# joyAnalog.net
KiCad netlist of a schematic drawn in EAGLE
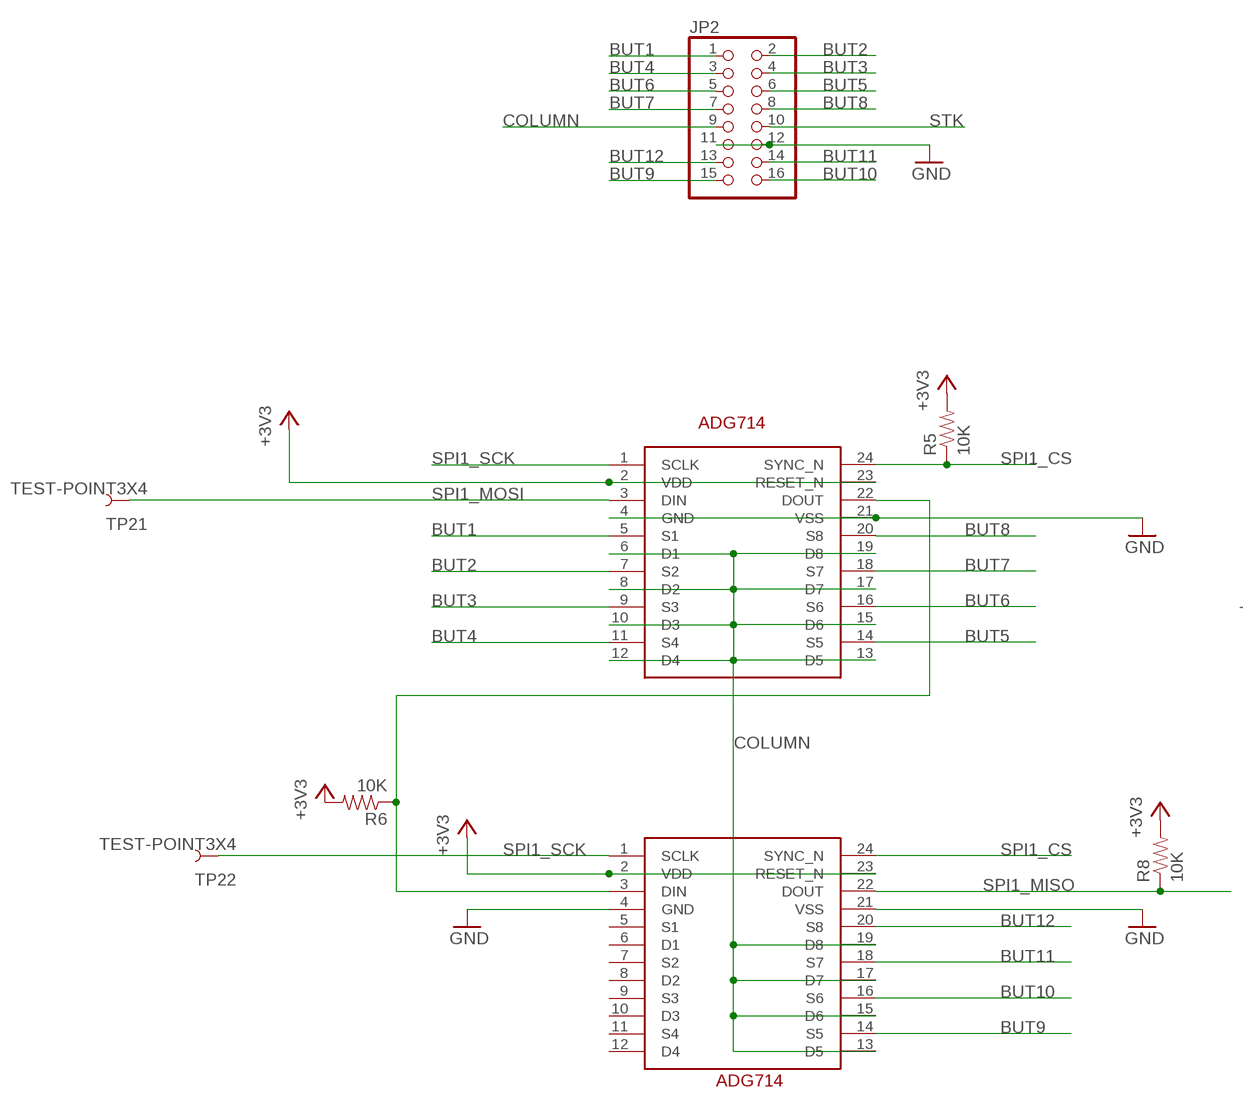
[diagram p0: schematic, sheet 1, part 1 of 2]
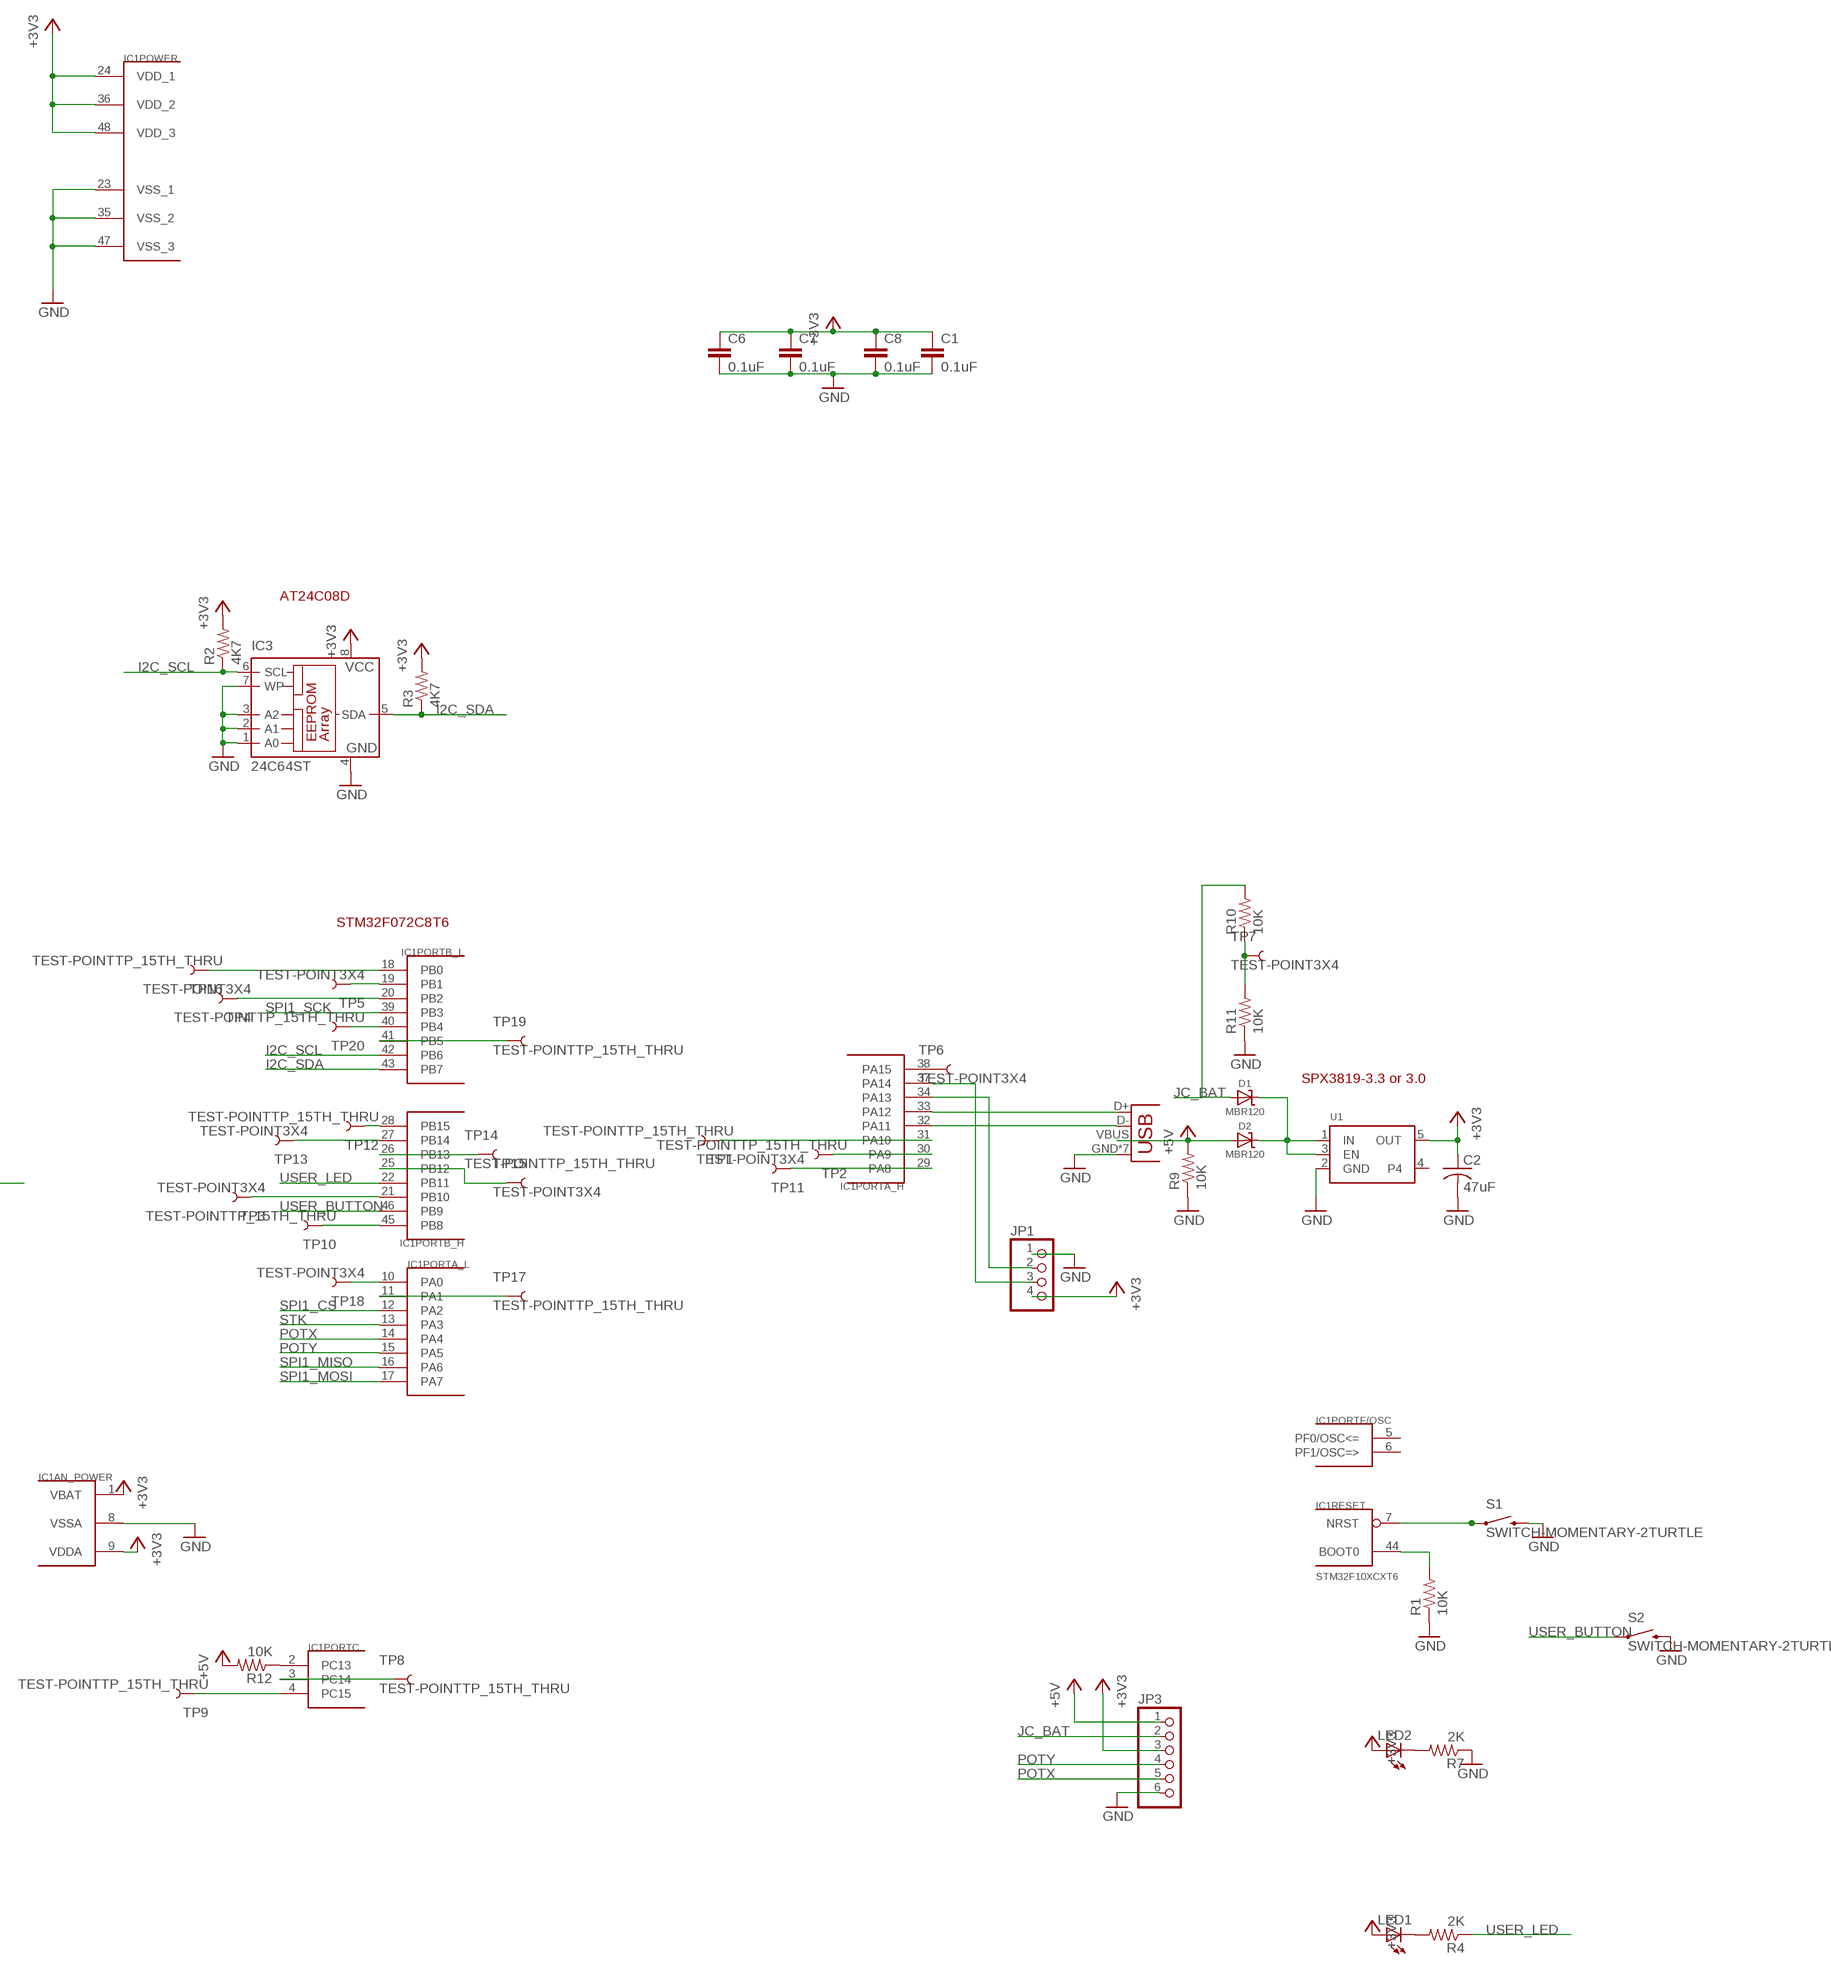
[diagram p1: schematic, sheet 1, part 2 of 2]

(export (version "E")
  (design (tool "Eeschema 10.0.6"))
  (components
    (comp (ref "C1")
      (value "0.1uF")
      (footprint "eagle-import:0805")
      (libsource (lib "eagle-import") (part "CAP0805"))
    )
    (comp (ref "C2")
      (value "47uF")
      (footprint "eagle-import:C1210")
      (libsource (lib "eagle-import") (part "C-USC1210"))
    )
    (comp (ref "C6")
      (value "0.1uF")
      (footprint "eagle-import:0805")
      (libsource (lib "eagle-import") (part "CAP0805"))
    )
    (comp (ref "C7")
      (value "0.1uF")
      (footprint "eagle-import:0805")
      (libsource (lib "eagle-import") (part "CAP0805"))
    )
    (comp (ref "C8")
      (value "0.1uF")
      (footprint "eagle-import:0805")
      (libsource (lib "eagle-import") (part "CAP0805"))
    )
    (comp (ref "D1")
      (value "MBR120")
      (footprint "eagle-import:SOD-123")
      (libsource (lib "eagle-import") (part "DIODE-SCHOTTKYSOD-123"))
    )
    (comp (ref "D2")
      (value "MBR120")
      (footprint "eagle-import:SOD-123")
      (libsource (lib "eagle-import") (part "DIODE-SCHOTTKYSOD-123"))
    )
    (comp (ref "IC1")
      (value "STM32F10XCXT6")
      (footprint "eagle-import:TQFP48")
      (libsource (lib "eagle-import") (part "STM32F10XCXT6"))
    )
    (comp (ref "IC3")
      (value "24C64ST")
      (footprint "eagle-import:TSSOP8")
      (fields (field (name "MPN") "CAT24C64YI-GT3"))
      (libsource (lib "eagle-import") (part "24STC64"))
    )
    (comp (ref "JP1")
      (value "PINHD-1X4")
      (footprint "eagle-import:1X04")
      (libsource (lib "eagle-import") (part "PINHD-1X4"))
    )
    (comp (ref "JP2")
      (value "PINHD-2X8")
      (footprint "eagle-import:2X08")
      (libsource (lib "eagle-import") (part "PINHD-2X8"))
    )
    (comp (ref "JP3")
      (value "PINHD-1X6CB")
      (footprint "eagle-import:1X06-CLEANBIG")
      (libsource (lib "eagle-import") (part "PINHD-1X6CB"))
    )
    (comp (ref "LED1")
      (value "LEDCHIP-LED0805")
      (footprint "eagle-import:CHIP-LED0805")
      (libsource (lib "eagle-import") (part "LEDCHIP-LED0805"))
    )
    (comp (ref "LED2")
      (value "LEDCHIP-LED0805")
      (footprint "eagle-import:CHIP-LED0805")
      (libsource (lib "eagle-import") (part "LEDCHIP-LED0805"))
    )
    (comp (ref "R1")
      (value "10K")
      (footprint "eagle-import:0805")
      (libsource (lib "eagle-import") (part "RESISTOR0805-RES"))
    )
    (comp (ref "R2")
      (value "4K7")
      (footprint "eagle-import:0805")
      (libsource (lib "eagle-import") (part "RESISTOR0805-RES"))
    )
    (comp (ref "R3")
      (value "4K7")
      (footprint "eagle-import:0805")
      (libsource (lib "eagle-import") (part "RESISTOR0805-RES"))
    )
    (comp (ref "R4")
      (value "2K")
      (footprint "eagle-import:0805")
      (libsource (lib "eagle-import") (part "RESISTOR0805-RES"))
    )
    (comp (ref "R5")
      (value "10K")
      (footprint "eagle-import:0805")
      (libsource (lib "eagle-import") (part "RESISTOR0805-RES"))
    )
    (comp (ref "R6")
      (value "10K")
      (footprint "eagle-import:0805")
      (libsource (lib "eagle-import") (part "RESISTOR0805-RES"))
    )
    (comp (ref "R7")
      (value "2K")
      (footprint "eagle-import:0805")
      (libsource (lib "eagle-import") (part "RESISTOR0805-RES"))
    )
    (comp (ref "R8")
      (value "10K")
      (footprint "eagle-import:0805")
      (libsource (lib "eagle-import") (part "RESISTOR0805-RES"))
    )
    (comp (ref "R9")
      (value "10K")
      (footprint "eagle-import:0805")
      (libsource (lib "eagle-import") (part "RESISTOR0805-RES"))
    )
    (comp (ref "R10")
      (value "10K")
      (footprint "eagle-import:0805")
      (libsource (lib "eagle-import") (part "RESISTOR0805-RES"))
    )
    (comp (ref "R11")
      (value "10K")
      (footprint "eagle-import:0805")
      (libsource (lib "eagle-import") (part "RESISTOR0805-RES"))
    )
    (comp (ref "R12")
      (value "10K")
      (footprint "eagle-import:0805")
      (libsource (lib "eagle-import") (part "RESISTOR0805-RES"))
    )
    (comp (ref "S1")
      (value "SWITCH-MOMENTARY-2TURTLE")
      (footprint "eagle-import:KMR2")
      (libsource (lib "eagle-import") (part "SWITCH-MOMENTARY-2TURTLE"))
    )
    (comp (ref "S2")
      (value "SWITCH-MOMENTARY-2TURTLE")
      (footprint "eagle-import:KMR2")
      (libsource (lib "eagle-import") (part "SWITCH-MOMENTARY-2TURTLE"))
    )
    (comp (ref "TP1")
      (value "TEST-POINTTP_15TH_THRU")
      (footprint "eagle-import:TP_15TH")
      (libsource (lib "eagle-import") (part "pth testpoint_TEST-POINTTP_15TH_THRU"))
    )
    (comp (ref "TP2")
      (value "TEST-POINTTP_15TH_THRU")
      (footprint "eagle-import:TP_15TH")
      (libsource (lib "eagle-import") (part "pth testpoint_TEST-POINTTP_15TH_THRU"))
    )
    (comp (ref "TP3")
      (value "TEST-POINT3X4")
      (footprint "eagle-import:PAD.03X.04")
      (libsource (lib "eagle-import") (part "TEST-POINT3X4"))
    )
    (comp (ref "TP4")
      (value "TEST-POINT3X4")
      (footprint "eagle-import:PAD.03X.04")
      (libsource (lib "eagle-import") (part "TEST-POINT3X4"))
    )
    (comp (ref "TP5")
      (value "TEST-POINT3X4")
      (footprint "eagle-import:PAD.03X.04")
      (libsource (lib "eagle-import") (part "TEST-POINT3X4"))
    )
    (comp (ref "TP6")
      (value "TEST-POINT3X4")
      (footprint "eagle-import:PAD.03X.04")
      (libsource (lib "eagle-import") (part "TEST-POINT3X4"))
    )
    (comp (ref "TP7")
      (value "TEST-POINT3X4")
      (footprint "eagle-import:PAD.03X.04")
      (libsource (lib "eagle-import") (part "TEST-POINT3X4"))
    )
    (comp (ref "TP8")
      (value "TEST-POINTTP_15TH_THRU")
      (footprint "eagle-import:TP_15TH")
      (libsource (lib "eagle-import") (part "pth testpoint_TEST-POINTTP_15TH_THRU"))
    )
    (comp (ref "TP9")
      (value "TEST-POINTTP_15TH_THRU")
      (footprint "eagle-import:TP_15TH")
      (libsource (lib "eagle-import") (part "pth testpoint_TEST-POINTTP_15TH_THRU"))
    )
    (comp (ref "TP10")
      (value "TEST-POINTTP_15TH_THRU")
      (footprint "eagle-import:TP_15TH")
      (libsource (lib "eagle-import") (part "pth testpoint_TEST-POINTTP_15TH_THRU"))
    )
    (comp (ref "TP11")
      (value "TEST-POINT3X4")
      (footprint "eagle-import:PAD.03X.04")
      (libsource (lib "eagle-import") (part "TEST-POINT3X4"))
    )
    (comp (ref "TP12")
      (value "TEST-POINTTP_15TH_THRU")
      (footprint "eagle-import:TP_15TH")
      (libsource (lib "eagle-import") (part "pth testpoint_TEST-POINTTP_15TH_THRU"))
    )
    (comp (ref "TP13")
      (value "TEST-POINT3X4")
      (footprint "eagle-import:PAD.03X.04")
      (libsource (lib "eagle-import") (part "TEST-POINT3X4"))
    )
    (comp (ref "TP14")
      (value "TEST-POINTTP_15TH_THRU")
      (footprint "eagle-import:TP_15TH")
      (libsource (lib "eagle-import") (part "pth testpoint_TEST-POINTTP_15TH_THRU"))
    )
    (comp (ref "TP15")
      (value "TEST-POINT3X4")
      (footprint "eagle-import:PAD.03X.04")
      (libsource (lib "eagle-import") (part "TEST-POINT3X4"))
    )
    (comp (ref "TP16")
      (value "TEST-POINTTP_15TH_THRU")
      (footprint "eagle-import:TP_15TH")
      (libsource (lib "eagle-import") (part "pth testpoint_TEST-POINTTP_15TH_THRU"))
    )
    (comp (ref "TP17")
      (value "TEST-POINTTP_15TH_THRU")
      (footprint "eagle-import:TP_15TH")
      (libsource (lib "eagle-import") (part "pth testpoint_TEST-POINTTP_15TH_THRU"))
    )
    (comp (ref "TP18")
      (value "TEST-POINT3X4")
      (footprint "eagle-import:PAD.03X.04")
      (libsource (lib "eagle-import") (part "TEST-POINT3X4"))
    )
    (comp (ref "TP19")
      (value "TEST-POINTTP_15TH_THRU")
      (footprint "eagle-import:TP_15TH")
      (libsource (lib "eagle-import") (part "pth testpoint_TEST-POINTTP_15TH_THRU"))
    )
    (comp (ref "TP20")
      (value "TEST-POINTTP_15TH_THRU")
      (footprint "eagle-import:TP_15TH")
      (libsource (lib "eagle-import") (part "pth testpoint_TEST-POINTTP_15TH_THRU"))
    )
    (comp (ref "TP21")
      (value "TEST-POINT3X4")
      (footprint "eagle-import:PAD.03X.04")
      (libsource (lib "eagle-import") (part "TEST-POINT3X4"))
    )
    (comp (ref "TP22")
      (value "TEST-POINT3X4")
      (footprint "eagle-import:PAD.03X.04")
      (libsource (lib "eagle-import") (part "TEST-POINT3X4"))
    )
    (comp (ref "U$3")
      (value "ADG714_DEV")
      (footprint "eagle-import:TSSOP-24")
      (libsource (lib "eagle-import") (part "ADG714_DEV"))
    )
    (comp (ref "U$4")
      (value "ADG714_DEV")
      (footprint "eagle-import:TSSOP-24")
      (libsource (lib "eagle-import") (part "ADG714_DEV"))
    )
    (comp (ref "U1")
      (value "VREG_SOT23-5")
      (footprint "eagle-import:SOT23-5")
      (libsource (lib "eagle-import") (part "VREG_SOT23-5"))
    )
    (comp (ref "X1")
      (value "USB-MICROB")
      (footprint "eagle-import:USB-MICROB")
      (libsource (lib "eagle-import") (part "USB-MICROB"))
    )
  )
  (nets
    (net (code "1") (name "+3V3") (class "Default")
      (node (ref "C1") (pin "1") (pinfunction "1_1") (pintype "passive"))
      (node (ref "C2") (pin "1") (pinfunction "1_1") (pintype "passive"))
      (node (ref "C6") (pin "1") (pinfunction "1_1") (pintype "passive"))
      (node (ref "C7") (pin "1") (pinfunction "1_1") (pintype "passive"))
      (node (ref "C8") (pin "1") (pinfunction "1_1") (pintype "passive"))
      (node (ref "IC1") (pin "1") (pinfunction "VBAT_1") (pintype "power_in"))
      (node (ref "IC1") (pin "24") (pinfunction "VDD_1_24") (pintype "power_in"))
      (node (ref "IC1") (pin "36") (pinfunction "VDD_2_36") (pintype "power_in"))
      (node (ref "IC1") (pin "48") (pinfunction "VDD_3_48") (pintype "power_in"))
      (node (ref "IC1") (pin "9") (pinfunction "VDDA_9") (pintype "power_in"))
      (node (ref "IC3") (pin "8") (pinfunction "VCC_8") (pintype "power_in"))
      (node (ref "JP1") (pin "4") (pinfunction "4_4") (pintype "passive"))
      (node (ref "JP3") (pin "3") (pinfunction "3_3") (pintype "passive"))
      (node (ref "LED1") (pin "A") (pinfunction "A_A") (pintype "passive"))
      (node (ref "LED2") (pin "A") (pinfunction "A_A") (pintype "passive"))
      (node (ref "R2") (pin "2") (pinfunction "2_2") (pintype "passive"))
      (node (ref "R3") (pin "2") (pinfunction "2_2") (pintype "passive"))
      (node (ref "R5") (pin "2") (pinfunction "2_2") (pintype "passive"))
      (node (ref "R6") (pin "2") (pinfunction "2_2") (pintype "passive"))
      (node (ref "R8") (pin "2") (pinfunction "2_2") (pintype "passive"))
      (node (ref "U$3") (pin "2") (pinfunction "VDD_2") (pintype "bidirectional"))
      (node (ref "U$3") (pin "23") (pinfunction "RESET_N_23") (pintype "bidirectional"))
      (node (ref "U$4") (pin "2") (pinfunction "VDD_2") (pintype "bidirectional"))
      (node (ref "U$4") (pin "23") (pinfunction "RESET_N_23") (pintype "bidirectional"))
      (node (ref "U1") (pin "5") (pinfunction "OUT_5") (pintype "power_in"))
    )
    (net (code "2") (name "+5V") (class "Default")
      (node (ref "D2") (pin "A") (pinfunction "A_A") (pintype "passive"))
      (node (ref "JP3") (pin "1") (pinfunction "1_1") (pintype "passive"))
      (node (ref "R12") (pin "2") (pinfunction "2_2") (pintype "passive"))
      (node (ref "R9") (pin "2") (pinfunction "2_2") (pintype "passive"))
      (node (ref "X1") (pin "VBUS") (pinfunction "VBUS_VBUS") (pintype "bidirectional"))
    )
    (net (code "3") (name "/BUT1") (class "Default")
      (node (ref "JP2") (pin "1") (pinfunction "1_1") (pintype "passive"))
      (node (ref "U$3") (pin "5") (pinfunction "S1_5") (pintype "bidirectional"))
    )
    (net (code "4") (name "/BUT2") (class "Default")
      (node (ref "JP2") (pin "2") (pinfunction "2_2") (pintype "passive"))
      (node (ref "U$3") (pin "7") (pinfunction "S2_7") (pintype "bidirectional"))
    )
    (net (code "5") (name "/BUT3") (class "Default")
      (node (ref "JP2") (pin "4") (pinfunction "4_4") (pintype "passive"))
      (node (ref "U$3") (pin "9") (pinfunction "S3_9") (pintype "bidirectional"))
    )
    (net (code "6") (name "/BUT4") (class "Default")
      (node (ref "JP2") (pin "3") (pinfunction "3_3") (pintype "passive"))
      (node (ref "U$3") (pin "11") (pinfunction "S4_11") (pintype "bidirectional"))
    )
    (net (code "7") (name "/BUT5") (class "Default")
      (node (ref "JP2") (pin "6") (pinfunction "6_6") (pintype "passive"))
      (node (ref "U$3") (pin "14") (pinfunction "S5_14") (pintype "bidirectional"))
    )
    (net (code "8") (name "/BUT6") (class "Default")
      (node (ref "JP2") (pin "5") (pinfunction "5_5") (pintype "passive"))
      (node (ref "U$3") (pin "16") (pinfunction "S6_16") (pintype "bidirectional"))
    )
    (net (code "9") (name "/BUT7") (class "Default")
      (node (ref "JP2") (pin "7") (pinfunction "7_7") (pintype "passive"))
      (node (ref "U$3") (pin "18") (pinfunction "S7_18") (pintype "bidirectional"))
    )
    (net (code "10") (name "/BUT8") (class "Default")
      (node (ref "JP2") (pin "8") (pinfunction "8_8") (pintype "passive"))
      (node (ref "U$3") (pin "20") (pinfunction "S8_20") (pintype "bidirectional"))
    )
    (net (code "11") (name "/BUT9") (class "Default")
      (node (ref "JP2") (pin "15") (pinfunction "15_15") (pintype "passive"))
      (node (ref "U$4") (pin "14") (pinfunction "S5_14") (pintype "bidirectional"))
    )
    (net (code "12") (name "/BUT10") (class "Default")
      (node (ref "JP2") (pin "16") (pinfunction "16_16") (pintype "passive"))
      (node (ref "U$4") (pin "16") (pinfunction "S6_16") (pintype "bidirectional"))
    )
    (net (code "13") (name "/BUT11") (class "Default")
      (node (ref "JP2") (pin "14") (pinfunction "14_14") (pintype "passive"))
      (node (ref "U$4") (pin "18") (pinfunction "S7_18") (pintype "bidirectional"))
    )
    (net (code "14") (name "/BUT12") (class "Default")
      (node (ref "JP2") (pin "13") (pinfunction "13_13") (pintype "passive"))
      (node (ref "U$4") (pin "20") (pinfunction "S8_20") (pintype "bidirectional"))
    )
    (net (code "15") (name "/COLUMN") (class "Default")
      (node (ref "JP2") (pin "9") (pinfunction "9_9") (pintype "passive"))
      (node (ref "U$3") (pin "10") (pinfunction "D3_10") (pintype "bidirectional"))
      (node (ref "U$3") (pin "12") (pinfunction "D4_12") (pintype "bidirectional"))
      (node (ref "U$3") (pin "13") (pinfunction "D5_13") (pintype "bidirectional"))
      (node (ref "U$3") (pin "15") (pinfunction "D6_15") (pintype "bidirectional"))
      (node (ref "U$3") (pin "17") (pinfunction "D7_17") (pintype "bidirectional"))
      (node (ref "U$3") (pin "19") (pinfunction "D8_19") (pintype "bidirectional"))
      (node (ref "U$3") (pin "6") (pinfunction "D1_6") (pintype "bidirectional"))
      (node (ref "U$3") (pin "8") (pinfunction "D2_8") (pintype "bidirectional"))
      (node (ref "U$4") (pin "13") (pinfunction "D5_13") (pintype "bidirectional"))
      (node (ref "U$4") (pin "15") (pinfunction "D6_15") (pintype "bidirectional"))
      (node (ref "U$4") (pin "17") (pinfunction "D7_17") (pintype "bidirectional"))
      (node (ref "U$4") (pin "19") (pinfunction "D8_19") (pintype "bidirectional"))
    )
    (net (code "16") (name "/I2C_SCL") (class "Default")
      (node (ref "IC1") (pin "42") (pinfunction "PB6_42") (pintype "bidirectional"))
      (node (ref "IC3") (pin "6") (pinfunction "SCL_6") (pintype "input"))
      (node (ref "R2") (pin "1") (pinfunction "1_1") (pintype "passive"))
    )
    (net (code "17") (name "/I2C_SDA") (class "Default")
      (node (ref "IC1") (pin "43") (pinfunction "PB7_43") (pintype "bidirectional"))
      (node (ref "IC3") (pin "5") (pinfunction "SDA_5") (pintype "bidirectional"))
      (node (ref "R3") (pin "1") (pinfunction "1_1") (pintype "passive"))
    )
    (net (code "18") (name "/JC_BAT") (class "Default")
      (node (ref "D1") (pin "A") (pinfunction "A_A") (pintype "passive"))
      (node (ref "JP3") (pin "2") (pinfunction "2_2") (pintype "passive"))
      (node (ref "R10") (pin "2") (pinfunction "2_2") (pintype "passive"))
    )
    (net (code "19") (name "/POTX") (class "Default")
      (node (ref "IC1") (pin "14") (pinfunction "PA4_14") (pintype "bidirectional"))
      (node (ref "JP3") (pin "5") (pinfunction "5_5") (pintype "passive"))
    )
    (net (code "20") (name "/POTY") (class "Default")
      (node (ref "IC1") (pin "15") (pinfunction "PA5_15") (pintype "bidirectional"))
      (node (ref "JP3") (pin "4") (pinfunction "4_4") (pintype "passive"))
    )
    (net (code "21") (name "/SPI1_CS") (class "Default")
      (node (ref "IC1") (pin "12") (pinfunction "PA2_12") (pintype "bidirectional"))
      (node (ref "R5") (pin "1") (pinfunction "1_1") (pintype "passive"))
      (node (ref "U$3") (pin "24") (pinfunction "SYNC_N_24") (pintype "bidirectional"))
      (node (ref "U$4") (pin "24") (pinfunction "SYNC_N_24") (pintype "bidirectional"))
    )
    (net (code "22") (name "/SPI1_MISO") (class "Default")
      (node (ref "IC1") (pin "16") (pinfunction "PA6_16") (pintype "bidirectional"))
      (node (ref "R8") (pin "1") (pinfunction "1_1") (pintype "passive"))
      (node (ref "U$4") (pin "22") (pinfunction "DOUT_22") (pintype "bidirectional"))
    )
    (net (code "23") (name "/SPI1_MOSI") (class "Default")
      (node (ref "IC1") (pin "17") (pinfunction "PA7_17") (pintype "bidirectional"))
      (node (ref "TP21") (pin "P$1") (pinfunction "1_P$1") (pintype "bidirectional"))
      (node (ref "U$3") (pin "3") (pinfunction "DIN_3") (pintype "bidirectional"))
    )
    (net (code "24") (name "/SPI1_SCK") (class "Default")
      (node (ref "IC1") (pin "39") (pinfunction "PB3_39") (pintype "bidirectional"))
      (node (ref "TP22") (pin "P$1") (pinfunction "1_P$1") (pintype "bidirectional"))
      (node (ref "U$3") (pin "1") (pinfunction "SCLK_1") (pintype "bidirectional"))
      (node (ref "U$4") (pin "1") (pinfunction "SCLK_1") (pintype "bidirectional"))
    )
    (net (code "25") (name "/STK") (class "Default")
      (node (ref "IC1") (pin "13") (pinfunction "PA3_13") (pintype "bidirectional"))
      (node (ref "JP2") (pin "10") (pinfunction "10_10") (pintype "passive"))
    )
    (net (code "26") (name "/USER_BUTTON") (class "Default")
      (node (ref "IC1") (pin "46") (pinfunction "PB9_46") (pintype "bidirectional"))
      (node (ref "S2") (pin "1") (pinfunction "1_1") (pintype "passive"))
    )
    (net (code "27") (name "/USER_LED") (class "Default")
      (node (ref "IC1") (pin "22") (pinfunction "PB11_22") (pintype "bidirectional"))
      (node (ref "R4") (pin "1") (pinfunction "1_1") (pintype "passive"))
    )
    (net (code "28") (name "GND") (class "Default")
      (node (ref "C1") (pin "2") (pinfunction "2_2") (pintype "passive"))
      (node (ref "C2") (pin "2") (pinfunction "2_2") (pintype "passive"))
      (node (ref "C6") (pin "2") (pinfunction "2_2") (pintype "passive"))
      (node (ref "C7") (pin "2") (pinfunction "2_2") (pintype "passive"))
      (node (ref "C8") (pin "2") (pinfunction "2_2") (pintype "passive"))
      (node (ref "IC1") (pin "23") (pinfunction "VSS_1_23") (pintype "power_in"))
      (node (ref "IC1") (pin "35") (pinfunction "VSS_2_35") (pintype "power_in"))
      (node (ref "IC1") (pin "47") (pinfunction "VSS_3_47") (pintype "power_in"))
      (node (ref "IC1") (pin "8") (pinfunction "VSSA_8") (pintype "power_in"))
      (node (ref "IC3") (pin "1") (pinfunction "A0_1") (pintype "input"))
      (node (ref "IC3") (pin "2") (pinfunction "A1_2") (pintype "input"))
      (node (ref "IC3") (pin "3") (pinfunction "A2_3") (pintype "input"))
      (node (ref "IC3") (pin "4") (pinfunction "GND_4") (pintype "power_in"))
      (node (ref "IC3") (pin "7") (pinfunction "WP_7") (pintype "input"))
      (node (ref "JP1") (pin "1") (pinfunction "1_1") (pintype "passive"))
      (node (ref "JP2") (pin "11") (pinfunction "11_11") (pintype "passive"))
      (node (ref "JP2") (pin "12") (pinfunction "12_12") (pintype "passive"))
      (node (ref "JP3") (pin "6") (pinfunction "6_6") (pintype "passive"))
      (node (ref "R1") (pin "1") (pinfunction "1_1") (pintype "passive"))
      (node (ref "R11") (pin "1") (pinfunction "1_1") (pintype "passive"))
      (node (ref "R7") (pin "1") (pinfunction "1_1") (pintype "passive"))
      (node (ref "R9") (pin "1") (pinfunction "1_1") (pintype "passive"))
      (node (ref "S1") (pin "3") (pinfunction "2_3") (pintype "passive"))
      (node (ref "S2") (pin "3") (pinfunction "2_3") (pintype "passive"))
      (node (ref "U$3") (pin "21") (pinfunction "VSS_21") (pintype "bidirectional"))
      (node (ref "U$3") (pin "4") (pinfunction "GND_4") (pintype "bidirectional"))
      (node (ref "U$4") (pin "21") (pinfunction "VSS_21") (pintype "bidirectional"))
      (node (ref "U$4") (pin "4") (pinfunction "GND_4") (pintype "bidirectional"))
      (node (ref "U1") (pin "2") (pinfunction "GND_2") (pintype "power_in"))
      (node (ref "X1") (pin "GND") (pinfunction "GND_GND") (pintype "bidirectional"))
      (node (ref "X1") (pin "P1") (pinfunction "GND_P1") (pintype "bidirectional"))
      (node (ref "X1") (pin "P2") (pinfunction "GND_P2") (pintype "bidirectional"))
      (node (ref "X1") (pin "P3") (pinfunction "GND_P3") (pintype "bidirectional"))
      (node (ref "X1") (pin "P4") (pinfunction "GND_P4") (pintype "bidirectional"))
      (node (ref "X1") (pin "P5") (pinfunction "GND_P5") (pintype "bidirectional"))
      (node (ref "X1") (pin "P6") (pinfunction "GND_P6") (pintype "bidirectional"))
    )
    (net (code "29") (name "Net-(IC1B-PA8)") (class "Default")
      (node (ref "IC1") (pin "29") (pinfunction "PA8_29") (pintype "bidirectional"))
      (node (ref "TP11") (pin "P$1") (pinfunction "1_P$1") (pintype "bidirectional"))
    )
    (net (code "30") (name "Net-(IC1B-PA9)") (class "Default")
      (node (ref "IC1") (pin "30") (pinfunction "PA9_30") (pintype "bidirectional"))
      (node (ref "TP2") (pin "P$1") (pinfunction "1_P$1") (pintype "bidirectional"))
    )
    (net (code "31") (name "Net-(IC1B-PA10)") (class "Default")
      (node (ref "IC1") (pin "31") (pinfunction "PA10_31") (pintype "bidirectional"))
      (node (ref "TP1") (pin "P$1") (pinfunction "1_P$1") (pintype "bidirectional"))
    )
    (net (code "32") (name "Net-(IC1B-PA11)") (class "Default")
      (node (ref "IC1") (pin "32") (pinfunction "PA11_32") (pintype "bidirectional"))
      (node (ref "X1") (pin "D-") (pinfunction "D-_D-") (pintype "bidirectional"))
    )
    (net (code "33") (name "Net-(IC1B-PA12)") (class "Default")
      (node (ref "IC1") (pin "33") (pinfunction "PA12_33") (pintype "bidirectional"))
      (node (ref "X1") (pin "D+") (pinfunction "D+_D+") (pintype "bidirectional"))
    )
    (net (code "34") (name "Net-(IC1B-PA13)") (class "Default")
      (node (ref "IC1") (pin "34") (pinfunction "PA13_34") (pintype "bidirectional"))
      (node (ref "JP1") (pin "2") (pinfunction "2_2") (pintype "passive"))
    )
    (net (code "35") (name "Net-(IC1B-PA14)") (class "Default")
      (node (ref "IC1") (pin "37") (pinfunction "PA14_37") (pintype "bidirectional"))
      (node (ref "JP1") (pin "3") (pinfunction "3_3") (pintype "passive"))
    )
    (net (code "36") (name "Net-(IC1B-PA15)") (class "Default")
      (node (ref "IC1") (pin "38") (pinfunction "PA15_38") (pintype "bidirectional"))
      (node (ref "TP6") (pin "P$1") (pinfunction "1_P$1") (pintype "bidirectional"))
    )
    (net (code "37") (name "Net-(IC1C-PA0)") (class "Default")
      (node (ref "IC1") (pin "10") (pinfunction "PA0_10") (pintype "bidirectional"))
      (node (ref "TP18") (pin "P$1") (pinfunction "1_P$1") (pintype "bidirectional"))
    )
    (net (code "38") (name "Net-(IC1C-PA1)") (class "Default")
      (node (ref "IC1") (pin "11") (pinfunction "PA1_11") (pintype "bidirectional"))
      (node (ref "TP17") (pin "P$1") (pinfunction "1_P$1") (pintype "bidirectional"))
    )
    (net (code "39") (name "Net-(IC1D-PB8)") (class "Default")
      (node (ref "IC1") (pin "45") (pinfunction "PB8_45") (pintype "bidirectional"))
      (node (ref "TP10") (pin "P$1") (pinfunction "1_P$1") (pintype "bidirectional"))
    )
    (net (code "40") (name "Net-(IC1D-PB10)") (class "Default")
      (node (ref "IC1") (pin "21") (pinfunction "PB10_21") (pintype "bidirectional"))
      (node (ref "TP3") (pin "P$1") (pinfunction "1_P$1") (pintype "bidirectional"))
    )
    (net (code "41") (name "Net-(IC1D-PB12)") (class "Default")
      (node (ref "IC1") (pin "25") (pinfunction "PB12_25") (pintype "bidirectional"))
      (node (ref "TP15") (pin "P$1") (pinfunction "1_P$1") (pintype "bidirectional"))
    )
    (net (code "42") (name "Net-(IC1D-PB13)") (class "Default")
      (node (ref "IC1") (pin "26") (pinfunction "PB13_26") (pintype "bidirectional"))
      (node (ref "TP14") (pin "P$1") (pinfunction "1_P$1") (pintype "bidirectional"))
    )
    (net (code "43") (name "Net-(IC1D-PB14)") (class "Default")
      (node (ref "IC1") (pin "27") (pinfunction "PB14_27") (pintype "bidirectional"))
      (node (ref "TP13") (pin "P$1") (pinfunction "1_P$1") (pintype "bidirectional"))
    )
    (net (code "44") (name "Net-(IC1D-PB15)") (class "Default")
      (node (ref "IC1") (pin "28") (pinfunction "PB15_28") (pintype "bidirectional"))
      (node (ref "TP12") (pin "P$1") (pinfunction "1_P$1") (pintype "bidirectional"))
    )
    (net (code "45") (name "Net-(IC1E-PB0)") (class "Default")
      (node (ref "IC1") (pin "18") (pinfunction "PB0_18") (pintype "bidirectional"))
      (node (ref "TP16") (pin "P$1") (pinfunction "1_P$1") (pintype "bidirectional"))
    )
    (net (code "46") (name "Net-(IC1E-PB1)") (class "Default")
      (node (ref "IC1") (pin "19") (pinfunction "PB1_19") (pintype "bidirectional"))
      (node (ref "TP5") (pin "P$1") (pinfunction "1_P$1") (pintype "bidirectional"))
    )
    (net (code "47") (name "Net-(IC1E-PB2)") (class "Default")
      (node (ref "IC1") (pin "20") (pinfunction "PB2_20") (pintype "bidirectional"))
      (node (ref "TP4") (pin "P$1") (pinfunction "1_P$1") (pintype "bidirectional"))
    )
    (net (code "48") (name "Net-(IC1E-PB4)") (class "Default")
      (node (ref "IC1") (pin "40") (pinfunction "PB4_40") (pintype "bidirectional"))
      (node (ref "TP20") (pin "P$1") (pinfunction "1_P$1") (pintype "bidirectional"))
    )
    (net (code "49") (name "Net-(IC1E-PB5)") (class "Default")
      (node (ref "IC1") (pin "41") (pinfunction "PB5_41") (pintype "bidirectional"))
      (node (ref "TP19") (pin "P$1") (pinfunction "1_P$1") (pintype "bidirectional"))
    )
    (net (code "50") (name "Net-(IC1F-PC13)") (class "Default")
      (node (ref "IC1") (pin "2") (pinfunction "PC13_2") (pintype "bidirectional"))
      (node (ref "R12") (pin "1") (pinfunction "1_1") (pintype "passive"))
    )
    (net (code "51") (name "Net-(IC1F-PC14)") (class "Default")
      (node (ref "IC1") (pin "3") (pinfunction "PC14_3") (pintype "bidirectional"))
      (node (ref "TP8") (pin "P$1") (pinfunction "1_P$1") (pintype "bidirectional"))
    )
    (net (code "52") (name "Net-(IC1F-PC15)") (class "Default")
      (node (ref "IC1") (pin "4") (pinfunction "PC15_4") (pintype "bidirectional"))
      (node (ref "TP9") (pin "P$1") (pinfunction "1_P$1") (pintype "bidirectional"))
    )
    (net (code "53") (name "Net-(IC1I-BOOT0)") (class "Default")
      (node (ref "IC1") (pin "44") (pinfunction "BOOT0_44") (pintype "input"))
      (node (ref "R1") (pin "2") (pinfunction "2_2") (pintype "passive"))
    )
    (net (code "54") (name "Net-(IC1I-NRST)") (class "Default")
      (node (ref "IC1") (pin "7") (pinfunction "NRST_7") (pintype "input"))
      (node (ref "S1") (pin "1") (pinfunction "1_1") (pintype "passive"))
    )
    (net (code "55") (name "Net-(LED1-PadC)") (class "Default")
      (node (ref "LED1") (pin "C") (pinfunction "C_C") (pintype "passive"))
      (node (ref "R4") (pin "2") (pinfunction "2_2") (pintype "passive"))
    )
    (net (code "56") (name "Net-(LED2-PadC)") (class "Default")
      (node (ref "LED2") (pin "C") (pinfunction "C_C") (pintype "passive"))
      (node (ref "R7") (pin "2") (pinfunction "2_2") (pintype "passive"))
    )
    (net (code "57") (name "Net-(TP7-1)") (class "Default")
      (node (ref "R10") (pin "1") (pinfunction "1_1") (pintype "passive"))
      (node (ref "R11") (pin "2") (pinfunction "2_2") (pintype "passive"))
      (node (ref "TP7") (pin "P$1") (pinfunction "1_P$1") (pintype "bidirectional"))
    )
    (net (code "58") (name "Net-(U$3-DOUT)") (class "Default")
      (node (ref "R6") (pin "1") (pinfunction "1_1") (pintype "passive"))
      (node (ref "U$3") (pin "22") (pinfunction "DOUT_22") (pintype "bidirectional"))
      (node (ref "U$4") (pin "3") (pinfunction "DIN_3") (pintype "bidirectional"))
    )
    (net (code "59") (name "Net-(U1-EN)") (class "Default")
      (node (ref "D1") (pin "C") (pinfunction "C_C") (pintype "passive"))
      (node (ref "D2") (pin "C") (pinfunction "C_C") (pintype "passive"))
      (node (ref "U1") (pin "1") (pinfunction "IN_1") (pintype "power_in"))
      (node (ref "U1") (pin "3") (pinfunction "EN_3") (pintype "input"))
    )
    (net (code "60") (name "unconnected-(IC1G-PF0{slash}OSC<=-Pad5)") (class "Default")
      (node (ref "IC1") (pin "5") (pinfunction "PF0/OSC<=_5") (pintype "bidirectional"))
    )
    (net (code "61") (name "unconnected-(IC1G-PF1{slash}OSC=>-Pad6)") (class "Default")
      (node (ref "IC1") (pin "6") (pinfunction "PF1/OSC=>_6") (pintype "bidirectional"))
    )
    (net (code "62") (name "unconnected-(U$4-D1-Pad6)") (class "Default")
      (node (ref "U$4") (pin "6") (pinfunction "D1_6") (pintype "bidirectional"))
    )
    (net (code "63") (name "unconnected-(U$4-D2-Pad8)") (class "Default")
      (node (ref "U$4") (pin "8") (pinfunction "D2_8") (pintype "bidirectional"))
    )
    (net (code "64") (name "unconnected-(U$4-D3-Pad10)") (class "Default")
      (node (ref "U$4") (pin "10") (pinfunction "D3_10") (pintype "bidirectional"))
    )
    (net (code "65") (name "unconnected-(U$4-D4-Pad12)") (class "Default")
      (node (ref "U$4") (pin "12") (pinfunction "D4_12") (pintype "bidirectional"))
    )
    (net (code "66") (name "unconnected-(U$4-S1-Pad5)") (class "Default")
      (node (ref "U$4") (pin "5") (pinfunction "S1_5") (pintype "bidirectional"))
    )
    (net (code "67") (name "unconnected-(U$4-S2-Pad7)") (class "Default")
      (node (ref "U$4") (pin "7") (pinfunction "S2_7") (pintype "bidirectional"))
    )
    (net (code "68") (name "unconnected-(U$4-S3-Pad9)") (class "Default")
      (node (ref "U$4") (pin "9") (pinfunction "S3_9") (pintype "bidirectional"))
    )
    (net (code "69") (name "unconnected-(U$4-S4-Pad11)") (class "Default")
      (node (ref "U$4") (pin "11") (pinfunction "S4_11") (pintype "bidirectional"))
    )
    (net (code "70") (name "unconnected-(U1-P4-Pad4)") (class "Default")
      (node (ref "U1") (pin "4") (pinfunction "P4_4") (pintype "bidirectional"))
    )
  )
)
